# pwir21-NUCLEO-adapter.net
KiCad netlist of a schematic drawn in Altium Designer
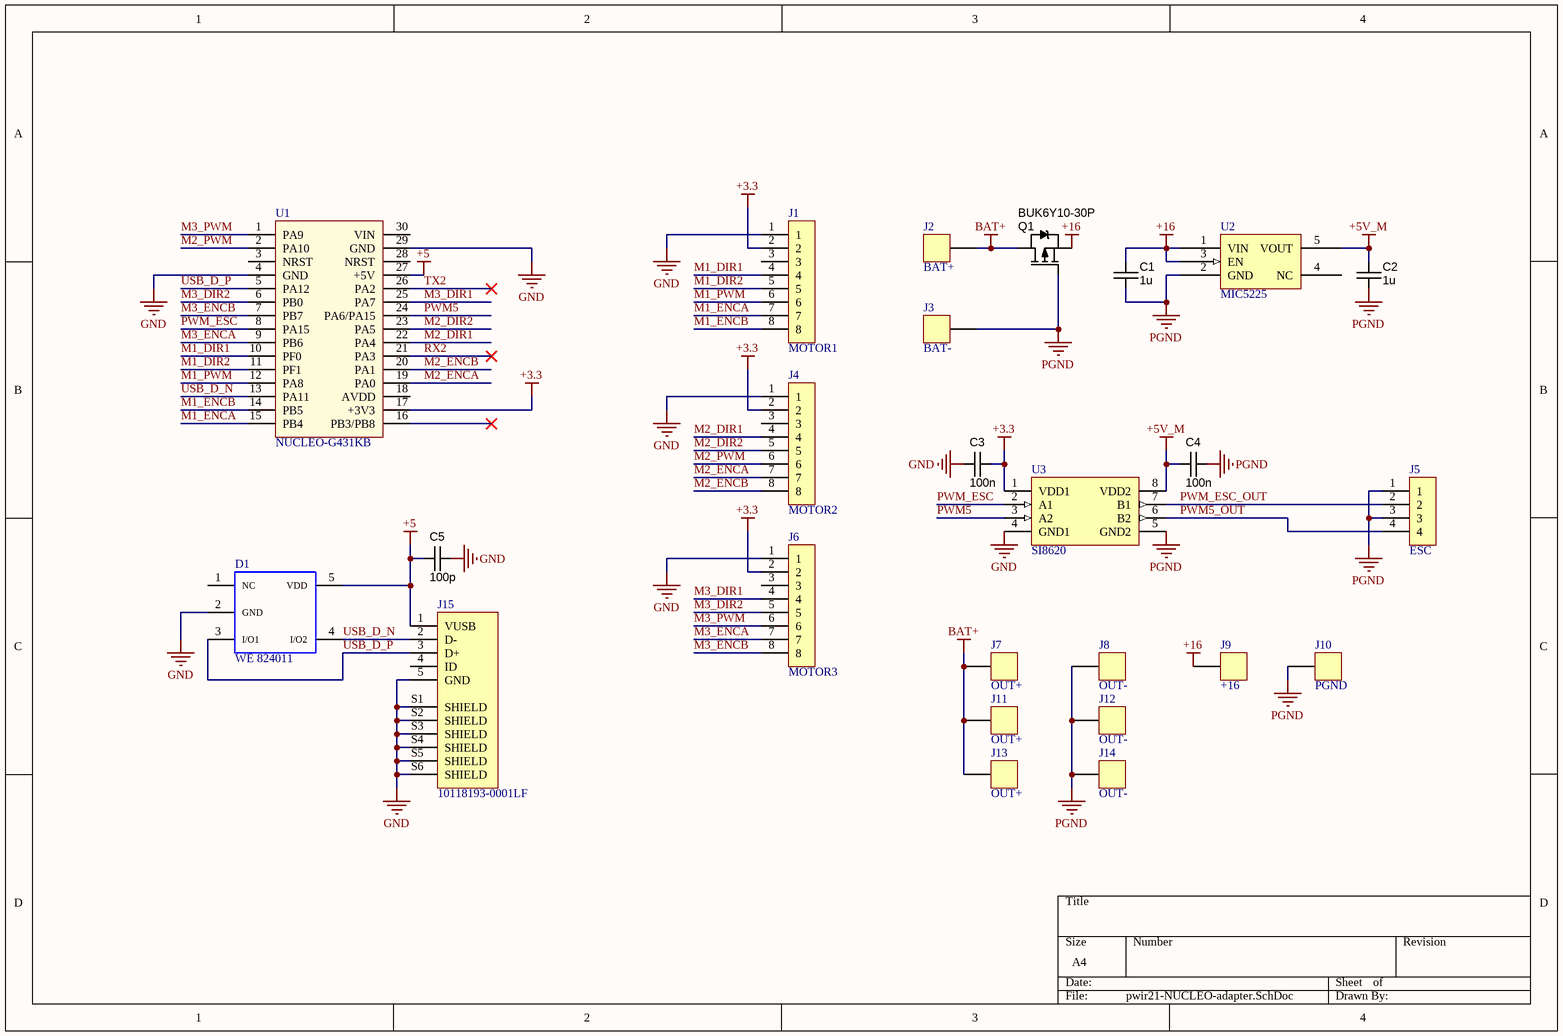
[diagram p0: pwir21-NUCLEO-adapter.SchDoc]

(export (version "E")
  (design (tool "Eeschema 10.0.6"))
  (components
    (comp (ref "C1")
      (value "1u")
      (footprint "CAPC1608X90N")
      (description "Capacitor SMD Cer 1uF 10% 16V X7R 0603")
      (fields (field (name "TOLERANCE") "±10%") (field (name "Comment") "approved sub OK"))
      (libsource (lib "PBL - Capacitors") (part "CAPC_1u_0603_X7R_16V_10%"))
    )
    (comp (ref "C2")
      (value "1u")
      (footprint "CAPC1608X90N")
      (description "Capacitor SMD Cer 1uF 10% 16V X7R 0603")
      (fields (field (name "TOLERANCE") "±10%") (field (name "Comment") "approved sub OK"))
      (libsource (lib "PBL - Capacitors") (part "CAPC_1u_0603_X7R_16V_10%"))
    )
    (comp (ref "C3")
      (value "100n")
      (footprint "CAPC1608X90N")
      (description "Capacitor SMD Cer 100nF 10% 50V X7R 0603")
      (fields (field (name "TOLERANCE") "±10%") (field (name "Comment") "approved sub OK"))
      (libsource (lib "PBL - Capacitors") (part "CAPC_100n_0603_X7R_50V_10%"))
    )
    (comp (ref "C4")
      (value "100n")
      (footprint "CAPC1608X90N")
      (description "Capacitor SMD Cer 100nF 10% 50V X7R 0603")
      (fields (field (name "TOLERANCE") "±10%") (field (name "Comment") "approved sub OK"))
      (libsource (lib "PBL - Capacitors") (part "CAPC_100n_0603_X7R_50V_10%"))
    )
    (comp (ref "C5")
      (value "100p")
      (footprint "CAPC1608X90N")
      (description "Capacitor SMD Cer 100pF 1% 50V NP0 0603")
      (fields (field (name "TOLERANCE") "±1%"))
      (libsource (lib "PBL - Capacitors") (part "CAPC_100p_0603_NP0_50V_1%"))
    )
    (comp (ref "D1")
      (value "WE 824011")
      (footprint "WE-TVS_SOT23-5L")
      (description "WE-TVS TVS Diode - High Speed Series, SOT23-5L, 2+1Channel, 5Vdc")
      (fields
        (field (name "MANUFACTURER PART NUMBER") "824011")
        (field (name "MANUFACTURER") "Wurth Elektronik")
      )
      (libsource (lib "Altium_WE-TVS_rev20a") (part "824011"))
    )
    (comp (ref "J1")
      (value "MOTOR1")
      (footprint "MICRO-MATCH-FOB-08")
      (libsource (lib "connectors_micromatch") (part "HEADER-8"))
    )
    (comp (ref "J2") (value "BAT+") (footprint "POWER-PAD-4x3") (libsource (lib "") (part "HEADER-1_1")))
    (comp (ref "J3") (value "BAT-") (footprint "POWER-PAD-4x3") (libsource (lib "") (part "HEADER-1_1")))
    (comp (ref "J4")
      (value "MOTOR2")
      (footprint "MICRO-MATCH-FOB-08")
      (libsource (lib "connectors_micromatch") (part "HEADER-8"))
    )
    (comp (ref "J5")
      (value "ESC")
      (footprint "MICRO-MATCH-FOB-04")
      (libsource (lib "connectors_micromatch") (part "HEADER-4"))
    )
    (comp (ref "J6")
      (value "MOTOR3")
      (footprint "MICRO-MATCH-FOB-08")
      (libsource (lib "connectors_micromatch") (part "HEADER-8"))
    )
    (comp (ref "J7")
      (value "OUT+")
      (footprint "POWER-PAD-4x3")
      (libsource (lib "connectors") (part "HEADER-1"))
    )
    (comp (ref "J8")
      (value "OUT-")
      (footprint "POWER-PAD-4x3")
      (libsource (lib "connectors") (part "HEADER-1"))
    )
    (comp (ref "J9")
      (value "+16")
      (footprint "POWER-PAD-4x3")
      (libsource (lib "connectors") (part "HEADER-1"))
    )
    (comp (ref "J10")
      (value "PGND")
      (footprint "POWER-PAD-4x3")
      (libsource (lib "connectors") (part "HEADER-1"))
    )
    (comp (ref "J11")
      (value "OUT+")
      (footprint "POWER-PAD-4x3")
      (libsource (lib "connectors") (part "HEADER-1"))
    )
    (comp (ref "J12")
      (value "OUT-")
      (footprint "POWER-PAD-4x3")
      (libsource (lib "connectors") (part "HEADER-1"))
    )
    (comp (ref "J13")
      (value "OUT+")
      (footprint "POWER-PAD-4x3")
      (libsource (lib "connectors") (part "HEADER-1"))
    )
    (comp (ref "J14")
      (value "OUT-")
      (footprint "POWER-PAD-4x3")
      (libsource (lib "connectors") (part "HEADER-1"))
    )
    (comp (ref "J15")
      (value "10118193-0001LF")
      (footprint "FCI_10118193-0001LF")
      (description "USB - micro B USB 2.0 Receptacle Connector 5 Position Surface Mount, Right Angle; Through Hole")
      (fields (field (name "MF") "Amphenol ICC"))
      (libsource (lib "connectors") (part "10118193-0001LF"))
    )
    (comp (ref "Q1") (value "BUK6Y10-30P") (footprint "SOT669") (libsource (lib "mosfets") (part "MOSFET-P")))
    (comp (ref "U1")
      (value "NUCLEO-G431KB")
      (footprint "NUCLEO-32-SMT")
      (libsource (lib "pwir21-NUCLEO-adapter") (part "NUCLEO-G431KB"))
    )
    (comp (ref "U2") (value "MIC5225") (footprint "SOT23-5") (libsource (lib "power") (part "LDO-SOT23-5")))
    (comp (ref "U3") (value "SI8620") (footprint "SOIC8") (libsource (lib "digital") (part "SI8620")))
  )
  (nets
    (net (code "1") (name "+3.3") (class "Default")
      (node (ref "C3") (pin "2") (pintype "passive"))
      (node (ref "J1") (pin "2") (pinfunction "2_2") (pintype "passive"))
      (node (ref "J4") (pin "2") (pinfunction "2_2") (pintype "passive"))
      (node (ref "J6") (pin "2") (pinfunction "2_2") (pintype "passive"))
      (node (ref "U1") (pin "17") (pinfunction "+3V3_17") (pintype "passive"))
      (node (ref "U3") (pin "1") (pinfunction "VDD1_1") (pintype "passive"))
    )
    (net (code "2") (name "+5") (class "Default")
      (node (ref "C5") (pin "2") (pintype "passive"))
      (node (ref "D1") (pin "5") (pinfunction "VDD_5") (pintype "passive"))
      (node (ref "J15") (pin "1") (pinfunction "VUSB_1") (pintype "passive"))
      (node (ref "U1") (pin "27") (pinfunction "+5V_27") (pintype "passive"))
    )
    (net (code "3") (name "+5V_M") (class "Default")
      (node (ref "C2") (pin "1") (pintype "passive"))
      (node (ref "C4") (pin "1") (pintype "passive"))
      (node (ref "U2") (pin "5") (pinfunction "VOUT_5") (pintype "passive"))
      (node (ref "U3") (pin "8") (pinfunction "VDD2_8") (pintype "passive"))
    )
    (net (code "4") (name "+16") (class "Default")
      (node (ref "C1") (pin "1") (pintype "passive"))
      (node (ref "J9") (pin "1") (pinfunction "1_1") (pintype "passive"))
      (node (ref "Q1") (pin "S") (pinfunction "S_S") (pintype "passive"))
      (node (ref "U2") (pin "1") (pinfunction "VIN_1") (pintype "power_in"))
      (node (ref "U2") (pin "3") (pinfunction "EN_3") (pintype "input"))
    )
    (net (code "5") (name "/M1_DIR1") (class "Default")
      (node (ref "J1") (pin "4") (pinfunction "4_4") (pintype "passive"))
      (node (ref "U1") (pin "10") (pinfunction "PF0_10") (pintype "passive"))
    )
    (net (code "6") (name "/M1_DIR2") (class "Default")
      (node (ref "J1") (pin "5") (pinfunction "5_5") (pintype "passive"))
      (node (ref "U1") (pin "11") (pinfunction "PF1_11") (pintype "passive"))
    )
    (net (code "7") (name "/M1_ENCA") (class "Default")
      (node (ref "J1") (pin "7") (pinfunction "7_7") (pintype "passive"))
      (node (ref "U1") (pin "15") (pinfunction "PB4_15") (pintype "passive"))
    )
    (net (code "8") (name "/M1_ENCB") (class "Default")
      (node (ref "J1") (pin "8") (pinfunction "8_8") (pintype "passive"))
      (node (ref "U1") (pin "14") (pinfunction "PB5_14") (pintype "passive"))
    )
    (net (code "9") (name "/M1_PWM") (class "Default")
      (node (ref "J1") (pin "6") (pinfunction "6_6") (pintype "passive"))
      (node (ref "U1") (pin "12") (pinfunction "PA8_12") (pintype "passive"))
    )
    (net (code "10") (name "/M2_DIR1") (class "Default")
      (node (ref "J4") (pin "4") (pinfunction "4_4") (pintype "passive"))
      (node (ref "U1") (pin "22") (pinfunction "PA4_22") (pintype "passive"))
    )
    (net (code "11") (name "/M2_DIR2") (class "Default")
      (node (ref "J4") (pin "5") (pinfunction "5_5") (pintype "passive"))
      (node (ref "U1") (pin "23") (pinfunction "PA5_23") (pintype "passive"))
    )
    (net (code "12") (name "/M2_ENCA") (class "Default")
      (node (ref "J4") (pin "7") (pinfunction "7_7") (pintype "passive"))
      (node (ref "U1") (pin "19") (pinfunction "PA0_19") (pintype "passive"))
    )
    (net (code "13") (name "/M2_ENCB") (class "Default")
      (node (ref "J4") (pin "8") (pinfunction "8_8") (pintype "passive"))
      (node (ref "U1") (pin "20") (pinfunction "PA1_20") (pintype "passive"))
    )
    (net (code "14") (name "/M2_PWM") (class "Default")
      (node (ref "J4") (pin "6") (pinfunction "6_6") (pintype "passive"))
      (node (ref "U1") (pin "2") (pinfunction "PA10_2") (pintype "passive"))
    )
    (net (code "15") (name "/M3_DIR1") (class "Default")
      (node (ref "J6") (pin "4") (pinfunction "4_4") (pintype "passive"))
      (node (ref "U1") (pin "25") (pinfunction "PA7_25") (pintype "passive"))
    )
    (net (code "16") (name "/M3_DIR2") (class "Default")
      (node (ref "J6") (pin "5") (pinfunction "5_5") (pintype "passive"))
      (node (ref "U1") (pin "6") (pinfunction "PB0_6") (pintype "passive"))
    )
    (net (code "17") (name "/M3_ENCA") (class "Default")
      (node (ref "J6") (pin "7") (pinfunction "7_7") (pintype "passive"))
      (node (ref "U1") (pin "9") (pinfunction "PB6_9") (pintype "passive"))
    )
    (net (code "18") (name "/M3_ENCB") (class "Default")
      (node (ref "J6") (pin "8") (pinfunction "8_8") (pintype "passive"))
      (node (ref "U1") (pin "7") (pinfunction "PB7_7") (pintype "passive"))
    )
    (net (code "19") (name "/M3_PWM") (class "Default")
      (node (ref "J6") (pin "6") (pinfunction "6_6") (pintype "passive"))
      (node (ref "U1") (pin "1") (pinfunction "PA9_1") (pintype "passive"))
    )
    (net (code "20") (name "/PWM5") (class "Default")
      (node (ref "U1") (pin "24") (pinfunction "PA6/PA15_24") (pintype "passive"))
      (node (ref "U3") (pin "3") (pinfunction "A2_3") (pintype "input"))
    )
    (net (code "21") (name "/PWM5_OUT") (class "Default")
      (node (ref "J5") (pin "4") (pinfunction "4_4") (pintype "passive"))
      (node (ref "U3") (pin "6") (pinfunction "B2_6") (pintype "output"))
    )
    (net (code "22") (name "/PWM_ESC") (class "Default")
      (node (ref "U1") (pin "8") (pinfunction "PA15_8") (pintype "passive"))
      (node (ref "U3") (pin "2") (pinfunction "A1_2") (pintype "input"))
    )
    (net (code "23") (name "/PWM_ESC_OUT") (class "Default")
      (node (ref "J5") (pin "2") (pinfunction "2_2") (pintype "passive"))
      (node (ref "U3") (pin "7") (pinfunction "B1_7") (pintype "output"))
    )
    (net (code "24") (name "/RX2") (class "Default")
      (node (ref "U1") (pin "21") (pinfunction "PA3_21") (pintype "passive+no_connect"))
    )
    (net (code "25") (name "/TX2") (class "Default")
      (node (ref "U1") (pin "26") (pinfunction "PA2_26") (pintype "passive+no_connect"))
    )
    (net (code "26") (name "/USB_D_N") (class "Default")
      (node (ref "D1") (pin "4") (pinfunction "I/O2_4") (pintype "passive"))
      (node (ref "J15") (pin "2") (pinfunction "D-_2") (pintype "passive"))
      (node (ref "U1") (pin "13") (pinfunction "PA11_13") (pintype "passive"))
    )
    (net (code "27") (name "/USB_D_P") (class "Default")
      (node (ref "D1") (pin "3") (pinfunction "I/O1_3") (pintype "passive"))
      (node (ref "J15") (pin "3") (pinfunction "D+_3") (pintype "passive"))
      (node (ref "U1") (pin "5") (pinfunction "PA12_5") (pintype "passive"))
    )
    (net (code "28") (name "BAT+") (class "Default")
      (node (ref "J11") (pin "1") (pinfunction "1_1") (pintype "passive"))
      (node (ref "J13") (pin "1") (pinfunction "1_1") (pintype "passive"))
      (node (ref "J2") (pin "1") (pinfunction "1_1") (pintype "passive"))
      (node (ref "J7") (pin "1") (pinfunction "1_1") (pintype "passive"))
      (node (ref "Q1") (pin "D") (pinfunction "D_D") (pintype "passive"))
    )
    (net (code "29") (name "GND") (class "Default")
      (node (ref "C3") (pin "1") (pintype "passive"))
      (node (ref "C5") (pin "1") (pintype "passive"))
      (node (ref "D1") (pin "2") (pinfunction "GND_2") (pintype "passive"))
      (node (ref "J1") (pin "1") (pinfunction "1_1") (pintype "passive"))
      (node (ref "J15") (pin "5") (pinfunction "GND_5") (pintype "passive"))
      (node (ref "J15") (pin "S1") (pinfunction "SHIELD_S1") (pintype "passive"))
      (node (ref "J15") (pin "S2") (pinfunction "SHIELD_S2") (pintype "passive"))
      (node (ref "J15") (pin "S3") (pinfunction "SHIELD_S3") (pintype "passive"))
      (node (ref "J15") (pin "S4") (pinfunction "SHIELD_S4") (pintype "passive"))
      (node (ref "J15") (pin "S5") (pinfunction "SHIELD_S5") (pintype "passive"))
      (node (ref "J15") (pin "S6") (pinfunction "SHIELD_S6") (pintype "passive"))
      (node (ref "J4") (pin "1") (pinfunction "1_1") (pintype "passive"))
      (node (ref "J6") (pin "1") (pinfunction "1_1") (pintype "passive"))
      (node (ref "U1") (pin "29") (pinfunction "GND_29") (pintype "passive"))
      (node (ref "U1") (pin "4") (pinfunction "GND_4") (pintype "passive"))
      (node (ref "U3") (pin "4") (pinfunction "GND1_4") (pintype "passive"))
    )
    (net (code "30") (name "PGND") (class "Default")
      (node (ref "C1") (pin "2") (pintype "passive"))
      (node (ref "C2") (pin "2") (pintype "passive"))
      (node (ref "C4") (pin "2") (pintype "passive"))
      (node (ref "J10") (pin "1") (pinfunction "1_1") (pintype "passive"))
      (node (ref "J12") (pin "1") (pinfunction "1_1") (pintype "passive"))
      (node (ref "J14") (pin "1") (pinfunction "1_1") (pintype "passive"))
      (node (ref "J3") (pin "1") (pinfunction "1_1") (pintype "passive"))
      (node (ref "J5") (pin "1") (pinfunction "1_1") (pintype "passive"))
      (node (ref "J5") (pin "3") (pinfunction "3_3") (pintype "passive"))
      (node (ref "J8") (pin "1") (pinfunction "1_1") (pintype "passive"))
      (node (ref "Q1") (pin "G") (pinfunction "G_G") (pintype "passive"))
      (node (ref "U2") (pin "2") (pinfunction "GND_2") (pintype "power_in"))
      (node (ref "U3") (pin "5") (pinfunction "GND2_5") (pintype "passive"))
    )
    (net (code "31") (name "unconnected-(D1-NC-Pad1)") (class "Default")
      (node (ref "D1") (pin "1") (pinfunction "NC_1") (pintype "passive"))
    )
    (net (code "32") (name "unconnected-(J1-Pad3)") (class "Default")
      (node (ref "J1") (pin "3") (pinfunction "3_3") (pintype "passive"))
    )
    (net (code "33") (name "unconnected-(J4-Pad3)") (class "Default")
      (node (ref "J4") (pin "3") (pinfunction "3_3") (pintype "passive"))
    )
    (net (code "34") (name "unconnected-(J6-Pad3)") (class "Default")
      (node (ref "J6") (pin "3") (pinfunction "3_3") (pintype "passive"))
    )
    (net (code "35") (name "unconnected-(J15-ID-Pad4)") (class "Default")
      (node (ref "J15") (pin "4") (pinfunction "ID_4") (pintype "passive"))
    )
    (net (code "36") (name "unconnected-(U1-AVDD-Pad18)") (class "Default")
      (node (ref "U1") (pin "18") (pinfunction "AVDD_18") (pintype "passive"))
    )
    (net (code "37") (name "unconnected-(U1-NRST-Pad3)") (class "Default")
      (node (ref "U1") (pin "3") (pinfunction "NRST_3") (pintype "passive"))
    )
    (net (code "38") (name "unconnected-(U1-NRST-Pad28)") (class "Default")
      (node (ref "U1") (pin "28") (pinfunction "NRST_28") (pintype "passive"))
    )
    (net (code "39") (name "unconnected-(U1-PB3{slash}PB8-Pad16)") (class "Default")
      (node (ref "U1") (pin "16") (pinfunction "PB3/PB8_16") (pintype "passive+no_connect"))
    )
    (net (code "40") (name "unconnected-(U1-VIN-Pad30)") (class "Default")
      (node (ref "U1") (pin "30") (pinfunction "VIN_30") (pintype "passive"))
    )
    (net (code "41") (name "unconnected-(U2-NC-Pad4)") (class "Default")
      (node (ref "U2") (pin "4") (pinfunction "NC_4") (pintype "power_in"))
    )
  )
)
